# CompleteBoardAlternative.net
KiCad netlist of a schematic drawn in EAGLE
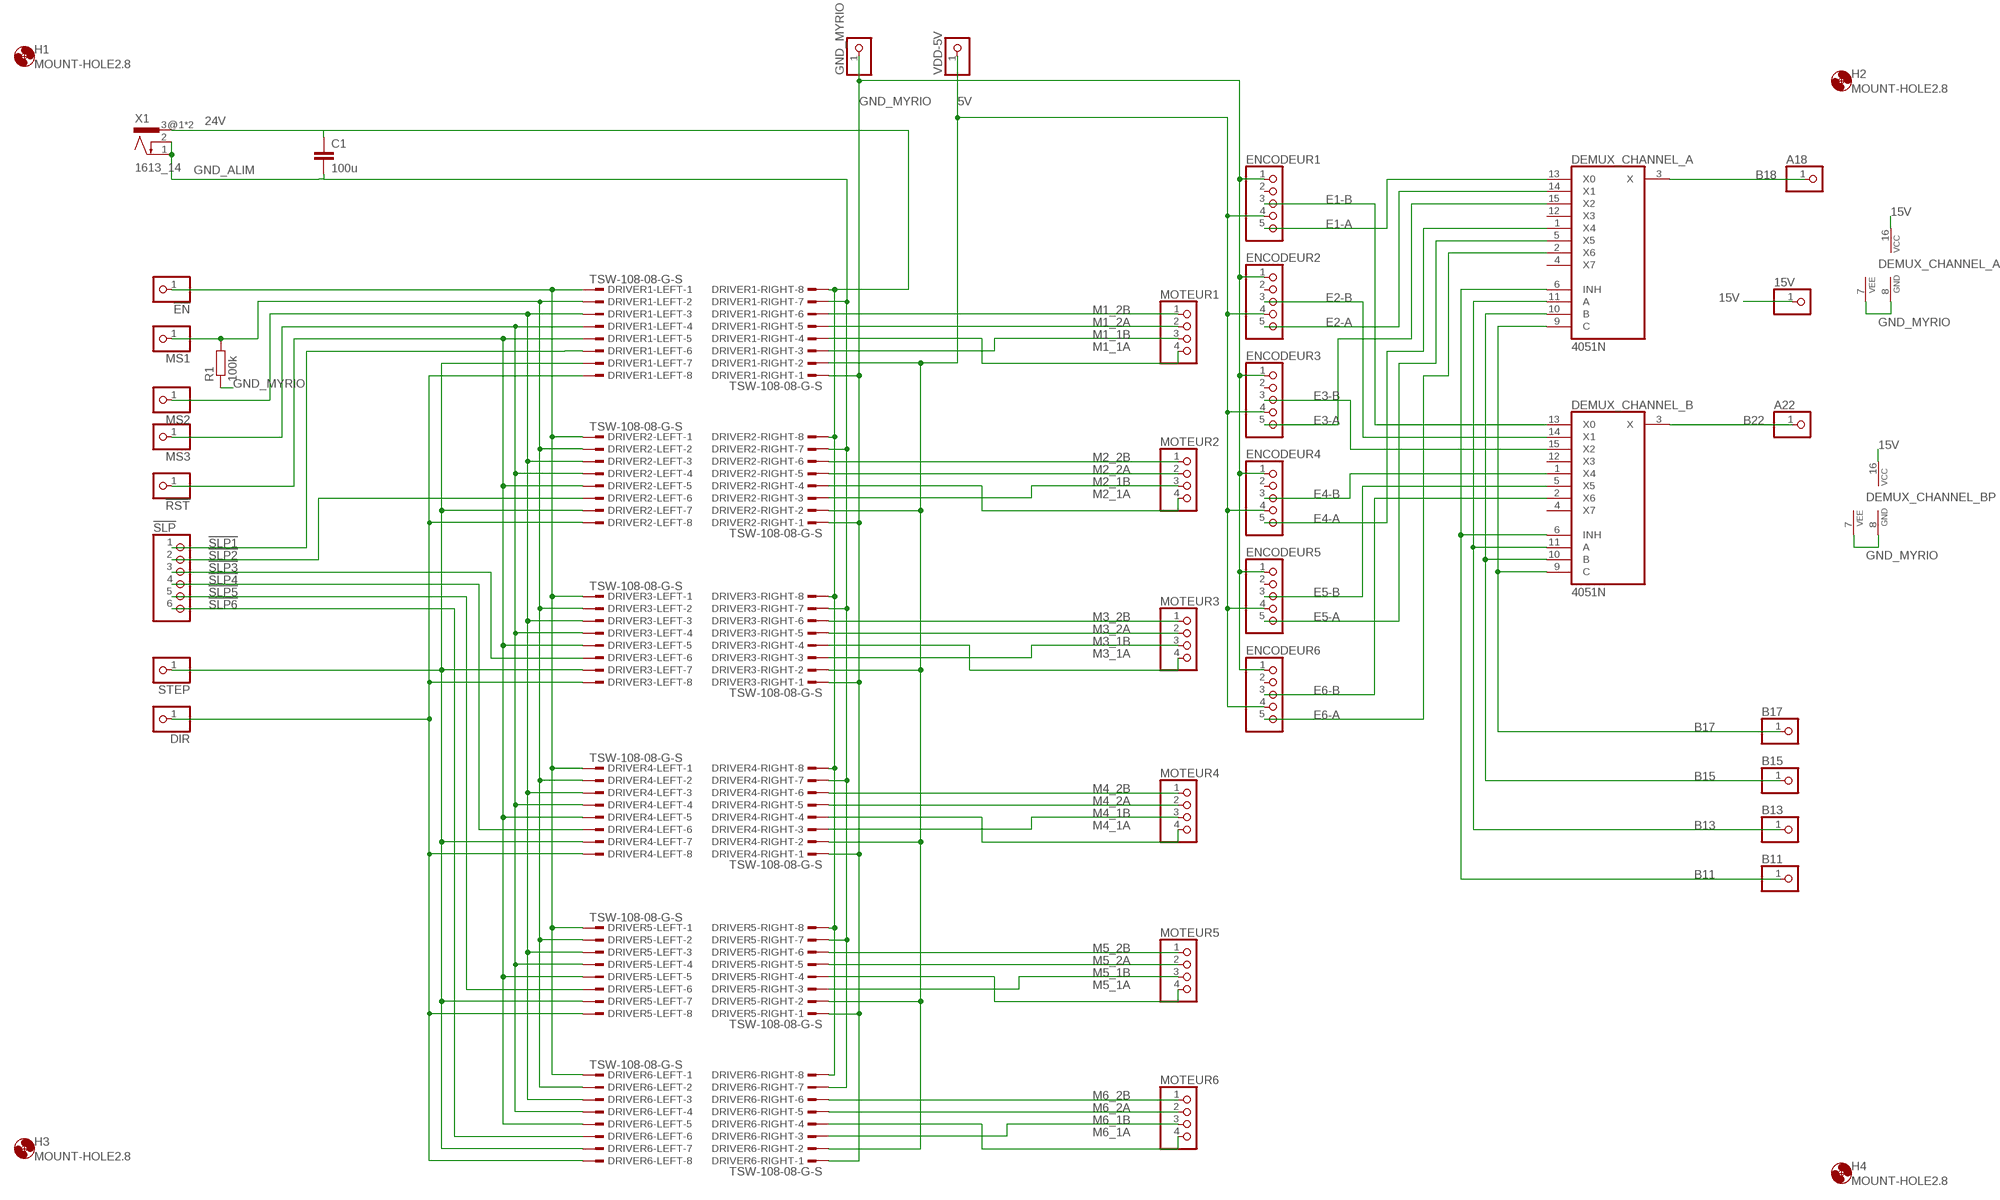
[diagram p0: schematic, sheet 1]

(export (version "E")
  (design (tool "Eeschema 10.0.6"))
  (components
    (comp (ref "!EN")
      (value "PINHD-1X1")
      (footprint "eagle-import:1X01")
      (libsource (lib "eagle-import") (part "PINHD-1X1"))
    )
    (comp (ref "!RST")
      (value "PINHD-1X1")
      (footprint "eagle-import:1X01")
      (libsource (lib "eagle-import") (part "PINHD-1X1"))
    )
    (comp (ref "!SLP")
      (value "PINHD-1X6")
      (footprint "eagle-import:1X06")
      (libsource (lib "eagle-import") (part "PINHD-1X6"))
    )
    (comp (ref "15V")
      (value "PINHD-1X1")
      (footprint "eagle-import:1X01")
      (libsource (lib "eagle-import") (part "PINHD-1X1"))
    )
    (comp (ref "A18")
      (value "PINHD-1X1")
      (footprint "eagle-import:1X01")
      (libsource (lib "eagle-import") (part "PINHD-1X1"))
    )
    (comp (ref "A22")
      (value "PINHD-1X1")
      (footprint "eagle-import:1X01")
      (libsource (lib "eagle-import") (part "PINHD-1X1"))
    )
    (comp (ref "B11")
      (value "PINHD-1X1")
      (footprint "eagle-import:1X01")
      (libsource (lib "eagle-import") (part "PINHD-1X1"))
    )
    (comp (ref "B13")
      (value "PINHD-1X1")
      (footprint "eagle-import:1X01")
      (libsource (lib "eagle-import") (part "PINHD-1X1"))
    )
    (comp (ref "B15")
      (value "PINHD-1X1")
      (footprint "eagle-import:1X01")
      (libsource (lib "eagle-import") (part "PINHD-1X1"))
    )
    (comp (ref "B17")
      (value "PINHD-1X1")
      (footprint "eagle-import:1X01")
      (libsource (lib "eagle-import") (part "PINHD-1X1"))
    )
    (comp (ref "C1")
      (value "100u")
      (footprint "eagle-import:C025-025X050")
      (libsource (lib "eagle-import") (part "C-EU025-025X050"))
    )
    (comp (ref "DEMUX_CHANNEL_A")
      (value "4051N")
      (footprint "eagle-import:DIL16")
      (libsource (lib "eagle-import") (part "4051N"))
    )
    (comp (ref "DEMUX_CHANNEL_B")
      (value "4051N")
      (footprint "eagle-import:DIL16")
      (libsource (lib "eagle-import") (part "4051N"))
    )
    (comp (ref "DIR")
      (value "PINHD-1X1")
      (footprint "eagle-import:1X01")
      (libsource (lib "eagle-import") (part "PINHD-1X1"))
    )
    (comp (ref "DRIVER1-LEFT")
      (value "TSW-108-08-G-S")
      (footprint "eagle-import:TSW-108-XX-G-S")
      (fields (field (name "MF") "Samtec Inc.") (field (name "MPN") "TSW-108-07-G-S"))
      (libsource (lib "eagle-import") (part "TSW-108--G-S08"))
    )
    (comp (ref "DRIVER1-RIGHT")
      (value "TSW-108-08-G-S")
      (footprint "eagle-import:TSW-108-XX-G-S")
      (fields (field (name "MF") "Samtec Inc.") (field (name "MPN") "TSW-108-07-G-S"))
      (libsource (lib "eagle-import") (part "TSW-108--G-S08"))
    )
    (comp (ref "DRIVER2-LEFT")
      (value "TSW-108-08-G-S")
      (footprint "eagle-import:TSW-108-XX-G-S")
      (fields (field (name "MF") "Samtec Inc.") (field (name "MPN") "TSW-108-07-G-S"))
      (libsource (lib "eagle-import") (part "TSW-108--G-S08"))
    )
    (comp (ref "DRIVER2-RIGHT")
      (value "TSW-108-08-G-S")
      (footprint "eagle-import:TSW-108-XX-G-S")
      (fields (field (name "MF") "Samtec Inc.") (field (name "MPN") "TSW-108-07-G-S"))
      (libsource (lib "eagle-import") (part "TSW-108--G-S08"))
    )
    (comp (ref "DRIVER3-LEFT")
      (value "TSW-108-08-G-S")
      (footprint "eagle-import:TSW-108-XX-G-S")
      (fields (field (name "MF") "Samtec Inc.") (field (name "MPN") "TSW-108-07-G-S"))
      (libsource (lib "eagle-import") (part "TSW-108--G-S08"))
    )
    (comp (ref "DRIVER3-RIGHT")
      (value "TSW-108-08-G-S")
      (footprint "eagle-import:TSW-108-XX-G-S")
      (fields (field (name "MF") "Samtec Inc.") (field (name "MPN") "TSW-108-07-G-S"))
      (libsource (lib "eagle-import") (part "TSW-108--G-S08"))
    )
    (comp (ref "DRIVER4-LEFT")
      (value "TSW-108-08-G-S")
      (footprint "eagle-import:TSW-108-XX-G-S")
      (fields (field (name "MF") "Samtec Inc.") (field (name "MPN") "TSW-108-07-G-S"))
      (libsource (lib "eagle-import") (part "TSW-108--G-S08"))
    )
    (comp (ref "DRIVER4-RIGHT")
      (value "TSW-108-08-G-S")
      (footprint "eagle-import:TSW-108-XX-G-S")
      (fields (field (name "MF") "Samtec Inc.") (field (name "MPN") "TSW-108-07-G-S"))
      (libsource (lib "eagle-import") (part "TSW-108--G-S08"))
    )
    (comp (ref "DRIVER5-LEFT")
      (value "TSW-108-08-G-S")
      (footprint "eagle-import:TSW-108-XX-G-S")
      (fields (field (name "MF") "Samtec Inc.") (field (name "MPN") "TSW-108-07-G-S"))
      (libsource (lib "eagle-import") (part "TSW-108--G-S08"))
    )
    (comp (ref "DRIVER5-RIGHT")
      (value "TSW-108-08-G-S")
      (footprint "eagle-import:TSW-108-XX-G-S")
      (fields (field (name "MF") "Samtec Inc.") (field (name "MPN") "TSW-108-07-G-S"))
      (libsource (lib "eagle-import") (part "TSW-108--G-S08"))
    )
    (comp (ref "DRIVER6-LEFT")
      (value "TSW-108-08-G-S")
      (footprint "eagle-import:TSW-108-XX-G-S")
      (fields (field (name "MF") "Samtec Inc.") (field (name "MPN") "TSW-108-07-G-S"))
      (libsource (lib "eagle-import") (part "TSW-108--G-S08"))
    )
    (comp (ref "DRIVER6-RIGHT")
      (value "TSW-108-08-G-S")
      (footprint "eagle-import:TSW-108-XX-G-S")
      (fields (field (name "MF") "Samtec Inc.") (field (name "MPN") "TSW-108-07-G-S"))
      (libsource (lib "eagle-import") (part "TSW-108--G-S08"))
    )
    (comp (ref "ENCODEUR1")
      (value "PINHD-1X5")
      (footprint "eagle-import:1X05")
      (libsource (lib "eagle-import") (part "PINHD-1X5"))
    )
    (comp (ref "ENCODEUR2")
      (value "PINHD-1X5")
      (footprint "eagle-import:1X05")
      (libsource (lib "eagle-import") (part "PINHD-1X5"))
    )
    (comp (ref "ENCODEUR3")
      (value "PINHD-1X5")
      (footprint "eagle-import:1X05")
      (libsource (lib "eagle-import") (part "PINHD-1X5"))
    )
    (comp (ref "ENCODEUR4")
      (value "PINHD-1X5")
      (footprint "eagle-import:1X05")
      (libsource (lib "eagle-import") (part "PINHD-1X5"))
    )
    (comp (ref "ENCODEUR5")
      (value "PINHD-1X5")
      (footprint "eagle-import:1X05")
      (libsource (lib "eagle-import") (part "PINHD-1X5"))
    )
    (comp (ref "ENCODEUR6")
      (value "PINHD-1X5")
      (footprint "eagle-import:1X05")
      (libsource (lib "eagle-import") (part "PINHD-1X5"))
    )
    (comp (ref "GND_MYRIO")
      (value "PINHD-1X1")
      (footprint "eagle-import:1X01")
      (libsource (lib "eagle-import") (part "PINHD-1X1"))
    )
    (comp (ref "H1")
      (value "MOUNT-HOLE2.8")
      (footprint "eagle-import:2,8")
      (libsource (lib "eagle-import") (part "MOUNT-HOLE2.8"))
    )
    (comp (ref "H2")
      (value "MOUNT-HOLE2.8")
      (footprint "eagle-import:2,8")
      (libsource (lib "eagle-import") (part "MOUNT-HOLE2.8"))
    )
    (comp (ref "H3")
      (value "MOUNT-HOLE2.8")
      (footprint "eagle-import:2,8")
      (libsource (lib "eagle-import") (part "MOUNT-HOLE2.8"))
    )
    (comp (ref "H4")
      (value "MOUNT-HOLE2.8")
      (footprint "eagle-import:2,8")
      (libsource (lib "eagle-import") (part "MOUNT-HOLE2.8"))
    )
    (comp (ref "MOTEUR1")
      (value "PINHD-1X4")
      (footprint "eagle-import:1X04")
      (libsource (lib "eagle-import") (part "PINHD-1X4"))
    )
    (comp (ref "MOTEUR2")
      (value "PINHD-1X4")
      (footprint "eagle-import:1X04")
      (libsource (lib "eagle-import") (part "PINHD-1X4"))
    )
    (comp (ref "MOTEUR3")
      (value "PINHD-1X4")
      (footprint "eagle-import:1X04")
      (libsource (lib "eagle-import") (part "PINHD-1X4"))
    )
    (comp (ref "MOTEUR4")
      (value "PINHD-1X4")
      (footprint "eagle-import:1X04")
      (libsource (lib "eagle-import") (part "PINHD-1X4"))
    )
    (comp (ref "MOTEUR5")
      (value "PINHD-1X4")
      (footprint "eagle-import:1X04")
      (libsource (lib "eagle-import") (part "PINHD-1X4"))
    )
    (comp (ref "MOTEUR6")
      (value "PINHD-1X4")
      (footprint "eagle-import:1X04")
      (libsource (lib "eagle-import") (part "PINHD-1X4"))
    )
    (comp (ref "MS1")
      (value "PINHD-1X1")
      (footprint "eagle-import:1X01")
      (libsource (lib "eagle-import") (part "PINHD-1X1"))
    )
    (comp (ref "MS2")
      (value "PINHD-1X1")
      (footprint "eagle-import:1X01")
      (libsource (lib "eagle-import") (part "PINHD-1X1"))
    )
    (comp (ref "MS3")
      (value "PINHD-1X1")
      (footprint "eagle-import:1X01")
      (libsource (lib "eagle-import") (part "PINHD-1X1"))
    )
    (comp (ref "R1")
      (value "100k")
      (footprint "eagle-import:0207_10")
      (libsource (lib "eagle-import") (part "R-EU_0207/10"))
    )
    (comp (ref "STEP")
      (value "PINHD-1X1")
      (footprint "eagle-import:1X01")
      (libsource (lib "eagle-import") (part "PINHD-1X1"))
    )
    (comp (ref "VDD-5V")
      (value "PINHD-1X1")
      (footprint "eagle-import:1X01")
      (libsource (lib "eagle-import") (part "PINHD-1X1"))
    )
    (comp (ref "X1")
      (value "1613_14")
      (footprint "eagle-import:1613_14")
      (fields (field (name "MF") "LUMBERG") (field (name "MPN") "1613 14"))
      (libsource (lib "eagle-import") (part "1613_14"))
    )
  )
  (nets
    (net (code "1") (name "/5V") (class "Default")
      (node (ref "DRIVER1-RIGHT") (pin "2") (pinfunction "1_2") (pintype "passive"))
      (node (ref "DRIVER2-RIGHT") (pin "2") (pinfunction "1_2") (pintype "passive"))
      (node (ref "DRIVER3-RIGHT") (pin "2") (pinfunction "1_2") (pintype "passive"))
      (node (ref "DRIVER4-RIGHT") (pin "2") (pinfunction "1_2") (pintype "passive"))
      (node (ref "DRIVER5-RIGHT") (pin "2") (pinfunction "1_2") (pintype "passive"))
      (node (ref "DRIVER6-RIGHT") (pin "2") (pinfunction "1_2") (pintype "passive"))
      (node (ref "ENCODEUR1") (pin "4") (pinfunction "4_4") (pintype "passive"))
      (node (ref "ENCODEUR2") (pin "4") (pinfunction "4_4") (pintype "passive"))
      (node (ref "ENCODEUR3") (pin "4") (pinfunction "4_4") (pintype "passive"))
      (node (ref "ENCODEUR4") (pin "4") (pinfunction "4_4") (pintype "passive"))
      (node (ref "ENCODEUR5") (pin "4") (pinfunction "4_4") (pintype "passive"))
      (node (ref "ENCODEUR6") (pin "4") (pinfunction "4_4") (pintype "passive"))
      (node (ref "VDD-5V") (pin "1") (pinfunction "1_1") (pintype "passive"))
    )
    (net (code "2") (name "/15V") (class "Default")
      (node (ref "15V") (pin "1") (pinfunction "1_1") (pintype "passive"))
      (node (ref "DEMUX_CHANNEL_A") (pin "16") (pinfunction "VCC_16") (pintype "power_in"))
      (node (ref "DEMUX_CHANNEL_B") (pin "16") (pinfunction "VCC_16") (pintype "power_in"))
    )
    (net (code "3") (name "/24V") (class "Default")
      (node (ref "C1") (pin "1") (pinfunction "1_1") (pintype "passive"))
      (node (ref "DRIVER1-RIGHT") (pin "8") (pinfunction "1_8") (pintype "passive"))
      (node (ref "DRIVER2-RIGHT") (pin "8") (pinfunction "1_8") (pintype "passive"))
      (node (ref "DRIVER3-RIGHT") (pin "8") (pinfunction "1_8") (pintype "passive"))
      (node (ref "DRIVER4-RIGHT") (pin "8") (pinfunction "1_8") (pintype "passive"))
      (node (ref "DRIVER5-RIGHT") (pin "8") (pinfunction "1_8") (pintype "passive"))
      (node (ref "DRIVER6-RIGHT") (pin "8") (pinfunction "1_8") (pintype "passive"))
      (node (ref "X1") (pin "3@1") (pinfunction "3_3@1") (pintype "passive"))
      (node (ref "X1") (pin "3@2") (pinfunction "3_3@2") (pintype "passive"))
    )
    (net (code "4") (name "/B11") (class "Default")
      (node (ref "B11") (pin "1") (pinfunction "1_1") (pintype "passive"))
      (node (ref "DEMUX_CHANNEL_A") (pin "6") (pinfunction "INH_6") (pintype "input"))
      (node (ref "DEMUX_CHANNEL_B") (pin "6") (pinfunction "INH_6") (pintype "input"))
    )
    (net (code "5") (name "/B13") (class "Default")
      (node (ref "B13") (pin "1") (pinfunction "1_1") (pintype "passive"))
      (node (ref "DEMUX_CHANNEL_A") (pin "11") (pinfunction "A_11") (pintype "input"))
      (node (ref "DEMUX_CHANNEL_B") (pin "11") (pinfunction "A_11") (pintype "input"))
    )
    (net (code "6") (name "/B15") (class "Default")
      (node (ref "B15") (pin "1") (pinfunction "1_1") (pintype "passive"))
      (node (ref "DEMUX_CHANNEL_A") (pin "10") (pinfunction "B_10") (pintype "input"))
      (node (ref "DEMUX_CHANNEL_B") (pin "10") (pinfunction "B_10") (pintype "input"))
    )
    (net (code "7") (name "/B17") (class "Default")
      (node (ref "B17") (pin "1") (pinfunction "1_1") (pintype "passive"))
      (node (ref "DEMUX_CHANNEL_A") (pin "9") (pinfunction "C_9") (pintype "input"))
      (node (ref "DEMUX_CHANNEL_B") (pin "9") (pinfunction "C_9") (pintype "input"))
    )
    (net (code "8") (name "/B18") (class "Default")
      (node (ref "A18") (pin "1") (pinfunction "1_1") (pintype "passive"))
      (node (ref "DEMUX_CHANNEL_A") (pin "3") (pinfunction "X_3") (pintype "bidirectional"))
    )
    (net (code "9") (name "/B22") (class "Default")
      (node (ref "A22") (pin "1") (pinfunction "1_1") (pintype "passive"))
      (node (ref "DEMUX_CHANNEL_B") (pin "3") (pinfunction "X_3") (pintype "bidirectional"))
    )
    (net (code "10") (name "/E1-A") (class "Default")
      (node (ref "DEMUX_CHANNEL_A") (pin "13") (pinfunction "X0_13") (pintype "bidirectional"))
      (node (ref "ENCODEUR1") (pin "5") (pinfunction "5_5") (pintype "passive"))
    )
    (net (code "11") (name "/E1-B") (class "Default")
      (node (ref "DEMUX_CHANNEL_B") (pin "13") (pinfunction "X0_13") (pintype "bidirectional"))
      (node (ref "ENCODEUR1") (pin "3") (pinfunction "3_3") (pintype "passive"))
    )
    (net (code "12") (name "/E2-A") (class "Default")
      (node (ref "DEMUX_CHANNEL_A") (pin "14") (pinfunction "X1_14") (pintype "bidirectional"))
      (node (ref "ENCODEUR2") (pin "5") (pinfunction "5_5") (pintype "passive"))
    )
    (net (code "13") (name "/E2-B") (class "Default")
      (node (ref "DEMUX_CHANNEL_B") (pin "14") (pinfunction "X1_14") (pintype "bidirectional"))
      (node (ref "ENCODEUR2") (pin "3") (pinfunction "3_3") (pintype "passive"))
    )
    (net (code "14") (name "/E3-A") (class "Default")
      (node (ref "DEMUX_CHANNEL_A") (pin "15") (pinfunction "X2_15") (pintype "bidirectional"))
      (node (ref "ENCODEUR3") (pin "5") (pinfunction "5_5") (pintype "passive"))
    )
    (net (code "15") (name "/E3-B") (class "Default")
      (node (ref "DEMUX_CHANNEL_B") (pin "15") (pinfunction "X2_15") (pintype "bidirectional"))
      (node (ref "ENCODEUR3") (pin "3") (pinfunction "3_3") (pintype "passive"))
    )
    (net (code "16") (name "/E4-A") (class "Default")
      (node (ref "DEMUX_CHANNEL_A") (pin "1") (pinfunction "X4_1") (pintype "bidirectional"))
      (node (ref "ENCODEUR4") (pin "5") (pinfunction "5_5") (pintype "passive"))
    )
    (net (code "17") (name "/E4-B") (class "Default")
      (node (ref "DEMUX_CHANNEL_B") (pin "1") (pinfunction "X4_1") (pintype "bidirectional"))
      (node (ref "ENCODEUR4") (pin "3") (pinfunction "3_3") (pintype "passive"))
    )
    (net (code "18") (name "/E5-A") (class "Default")
      (node (ref "DEMUX_CHANNEL_A") (pin "5") (pinfunction "X5_5") (pintype "bidirectional"))
      (node (ref "ENCODEUR5") (pin "5") (pinfunction "5_5") (pintype "passive"))
    )
    (net (code "19") (name "/E5-B") (class "Default")
      (node (ref "DEMUX_CHANNEL_B") (pin "5") (pinfunction "X5_5") (pintype "bidirectional"))
      (node (ref "ENCODEUR5") (pin "3") (pinfunction "3_3") (pintype "passive"))
    )
    (net (code "20") (name "/E6-A") (class "Default")
      (node (ref "DEMUX_CHANNEL_A") (pin "2") (pinfunction "X6_2") (pintype "bidirectional"))
      (node (ref "ENCODEUR6") (pin "5") (pinfunction "5_5") (pintype "passive"))
    )
    (net (code "21") (name "/E6-B") (class "Default")
      (node (ref "DEMUX_CHANNEL_B") (pin "2") (pinfunction "X6_2") (pintype "bidirectional"))
      (node (ref "ENCODEUR6") (pin "3") (pinfunction "3_3") (pintype "passive"))
    )
    (net (code "22") (name "/GND_ALIM") (class "Default")
      (node (ref "C1") (pin "2") (pinfunction "2_2") (pintype "passive"))
      (node (ref "DRIVER1-RIGHT") (pin "7") (pinfunction "1_7") (pintype "passive"))
      (node (ref "DRIVER2-RIGHT") (pin "7") (pinfunction "1_7") (pintype "passive"))
      (node (ref "DRIVER3-RIGHT") (pin "7") (pinfunction "1_7") (pintype "passive"))
      (node (ref "DRIVER4-RIGHT") (pin "7") (pinfunction "1_7") (pintype "passive"))
      (node (ref "DRIVER5-RIGHT") (pin "7") (pinfunction "1_7") (pintype "passive"))
      (node (ref "DRIVER6-RIGHT") (pin "7") (pinfunction "1_7") (pintype "passive"))
      (node (ref "X1") (pin "1") (pinfunction "1_1") (pintype "passive"))
      (node (ref "X1") (pin "2") (pinfunction "2_2") (pintype "passive"))
    )
    (net (code "23") (name "/GND_MYRIO") (class "Default")
      (node (ref "DEMUX_CHANNEL_A") (pin "7") (pinfunction "VEE_7") (pintype "power_in"))
      (node (ref "DEMUX_CHANNEL_A") (pin "8") (pinfunction "GND_8") (pintype "power_in"))
      (node (ref "DEMUX_CHANNEL_B") (pin "7") (pinfunction "VEE_7") (pintype "power_in"))
      (node (ref "DEMUX_CHANNEL_B") (pin "8") (pinfunction "GND_8") (pintype "power_in"))
      (node (ref "DRIVER1-RIGHT") (pin "1") (pinfunction "1_1") (pintype "passive"))
      (node (ref "DRIVER2-RIGHT") (pin "1") (pinfunction "1_1") (pintype "passive"))
      (node (ref "DRIVER3-RIGHT") (pin "1") (pinfunction "1_1") (pintype "passive"))
      (node (ref "DRIVER4-RIGHT") (pin "1") (pinfunction "1_1") (pintype "passive"))
      (node (ref "DRIVER5-RIGHT") (pin "1") (pinfunction "1_1") (pintype "passive"))
      (node (ref "DRIVER6-RIGHT") (pin "1") (pinfunction "1_1") (pintype "passive"))
      (node (ref "ENCODEUR1") (pin "1") (pinfunction "1_1") (pintype "passive"))
      (node (ref "ENCODEUR2") (pin "1") (pinfunction "1_1") (pintype "passive"))
      (node (ref "ENCODEUR3") (pin "1") (pinfunction "1_1") (pintype "passive"))
      (node (ref "ENCODEUR4") (pin "1") (pinfunction "1_1") (pintype "passive"))
      (node (ref "ENCODEUR5") (pin "1") (pinfunction "1_1") (pintype "passive"))
      (node (ref "ENCODEUR6") (pin "1") (pinfunction "1_1") (pintype "passive"))
      (node (ref "GND_MYRIO") (pin "1") (pinfunction "1_1") (pintype "passive"))
      (node (ref "R1") (pin "1") (pinfunction "1_1") (pintype "passive"))
    )
    (net (code "24") (name "/M1_1A") (class "Default")
      (node (ref "DRIVER1-RIGHT") (pin "4") (pinfunction "1_4") (pintype "passive"))
      (node (ref "MOTEUR1") (pin "4") (pinfunction "4_4") (pintype "passive"))
    )
    (net (code "25") (name "/M1_1B") (class "Default")
      (node (ref "DRIVER1-RIGHT") (pin "3") (pinfunction "1_3") (pintype "passive"))
      (node (ref "MOTEUR1") (pin "3") (pinfunction "3_3") (pintype "passive"))
    )
    (net (code "26") (name "/M1_2A") (class "Default")
      (node (ref "DRIVER1-RIGHT") (pin "5") (pinfunction "1_5") (pintype "passive"))
      (node (ref "MOTEUR1") (pin "2") (pinfunction "2_2") (pintype "passive"))
    )
    (net (code "27") (name "/M1_2B") (class "Default")
      (node (ref "DRIVER1-RIGHT") (pin "6") (pinfunction "1_6") (pintype "passive"))
      (node (ref "MOTEUR1") (pin "1") (pinfunction "1_1") (pintype "passive"))
    )
    (net (code "28") (name "/M2_1A") (class "Default")
      (node (ref "DRIVER2-RIGHT") (pin "4") (pinfunction "1_4") (pintype "passive"))
      (node (ref "MOTEUR2") (pin "4") (pinfunction "4_4") (pintype "passive"))
    )
    (net (code "29") (name "/M2_1B") (class "Default")
      (node (ref "DRIVER2-RIGHT") (pin "3") (pinfunction "1_3") (pintype "passive"))
      (node (ref "MOTEUR2") (pin "3") (pinfunction "3_3") (pintype "passive"))
    )
    (net (code "30") (name "/M2_2A") (class "Default")
      (node (ref "DRIVER2-RIGHT") (pin "5") (pinfunction "1_5") (pintype "passive"))
      (node (ref "MOTEUR2") (pin "2") (pinfunction "2_2") (pintype "passive"))
    )
    (net (code "31") (name "/M2_2B") (class "Default")
      (node (ref "DRIVER2-RIGHT") (pin "6") (pinfunction "1_6") (pintype "passive"))
      (node (ref "MOTEUR2") (pin "1") (pinfunction "1_1") (pintype "passive"))
    )
    (net (code "32") (name "/M3_1A") (class "Default")
      (node (ref "DRIVER3-RIGHT") (pin "4") (pinfunction "1_4") (pintype "passive"))
      (node (ref "MOTEUR3") (pin "4") (pinfunction "4_4") (pintype "passive"))
    )
    (net (code "33") (name "/M3_1B") (class "Default")
      (node (ref "DRIVER3-RIGHT") (pin "3") (pinfunction "1_3") (pintype "passive"))
      (node (ref "MOTEUR3") (pin "3") (pinfunction "3_3") (pintype "passive"))
    )
    (net (code "34") (name "/M3_2A") (class "Default")
      (node (ref "DRIVER3-RIGHT") (pin "5") (pinfunction "1_5") (pintype "passive"))
      (node (ref "MOTEUR3") (pin "2") (pinfunction "2_2") (pintype "passive"))
    )
    (net (code "35") (name "/M3_2B") (class "Default")
      (node (ref "DRIVER3-RIGHT") (pin "6") (pinfunction "1_6") (pintype "passive"))
      (node (ref "MOTEUR3") (pin "1") (pinfunction "1_1") (pintype "passive"))
    )
    (net (code "36") (name "/M4_1A") (class "Default")
      (node (ref "DRIVER4-RIGHT") (pin "4") (pinfunction "1_4") (pintype "passive"))
      (node (ref "MOTEUR4") (pin "4") (pinfunction "4_4") (pintype "passive"))
    )
    (net (code "37") (name "/M4_1B") (class "Default")
      (node (ref "DRIVER4-RIGHT") (pin "3") (pinfunction "1_3") (pintype "passive"))
      (node (ref "MOTEUR4") (pin "3") (pinfunction "3_3") (pintype "passive"))
    )
    (net (code "38") (name "/M4_2A") (class "Default")
      (node (ref "DRIVER4-RIGHT") (pin "5") (pinfunction "1_5") (pintype "passive"))
      (node (ref "MOTEUR4") (pin "2") (pinfunction "2_2") (pintype "passive"))
    )
    (net (code "39") (name "/M4_2B") (class "Default")
      (node (ref "DRIVER4-RIGHT") (pin "6") (pinfunction "1_6") (pintype "passive"))
      (node (ref "MOTEUR4") (pin "1") (pinfunction "1_1") (pintype "passive"))
    )
    (net (code "40") (name "/M5_1A") (class "Default")
      (node (ref "DRIVER5-RIGHT") (pin "4") (pinfunction "1_4") (pintype "passive"))
      (node (ref "MOTEUR5") (pin "4") (pinfunction "4_4") (pintype "passive"))
    )
    (net (code "41") (name "/M5_1B") (class "Default")
      (node (ref "DRIVER5-RIGHT") (pin "3") (pinfunction "1_3") (pintype "passive"))
      (node (ref "MOTEUR5") (pin "3") (pinfunction "3_3") (pintype "passive"))
    )
    (net (code "42") (name "/M5_2A") (class "Default")
      (node (ref "DRIVER5-RIGHT") (pin "5") (pinfunction "1_5") (pintype "passive"))
      (node (ref "MOTEUR5") (pin "2") (pinfunction "2_2") (pintype "passive"))
    )
    (net (code "43") (name "/M5_2B") (class "Default")
      (node (ref "DRIVER5-RIGHT") (pin "6") (pinfunction "1_6") (pintype "passive"))
      (node (ref "MOTEUR5") (pin "1") (pinfunction "1_1") (pintype "passive"))
    )
    (net (code "44") (name "/M6_1A") (class "Default")
      (node (ref "DRIVER6-RIGHT") (pin "4") (pinfunction "1_4") (pintype "passive"))
      (node (ref "MOTEUR6") (pin "4") (pinfunction "4_4") (pintype "passive"))
    )
    (net (code "45") (name "/M6_1B") (class "Default")
      (node (ref "DRIVER6-RIGHT") (pin "3") (pinfunction "1_3") (pintype "passive"))
      (node (ref "MOTEUR6") (pin "3") (pinfunction "3_3") (pintype "passive"))
    )
    (net (code "46") (name "/M6_2A") (class "Default")
      (node (ref "DRIVER6-RIGHT") (pin "5") (pinfunction "1_5") (pintype "passive"))
      (node (ref "MOTEUR6") (pin "2") (pinfunction "2_2") (pintype "passive"))
    )
    (net (code "47") (name "/M6_2B") (class "Default")
      (node (ref "DRIVER6-RIGHT") (pin "6") (pinfunction "1_6") (pintype "passive"))
      (node (ref "MOTEUR6") (pin "1") (pinfunction "1_1") (pintype "passive"))
    )
    (net (code "48") (name "/~{SLP1}") (class "Default")
      (node (ref "!SLP") (pin "1") (pinfunction "1_1") (pintype "passive"))
      (node (ref "DRIVER1-LEFT") (pin "6") (pinfunction "1_6") (pintype "passive"))
    )
    (net (code "49") (name "/~{SLP2}") (class "Default")
      (node (ref "!SLP") (pin "2") (pinfunction "2_2") (pintype "passive"))
      (node (ref "DRIVER2-LEFT") (pin "6") (pinfunction "1_6") (pintype "passive"))
    )
    (net (code "50") (name "/~{SLP3}") (class "Default")
      (node (ref "!SLP") (pin "3") (pinfunction "3_3") (pintype "passive"))
      (node (ref "DRIVER3-LEFT") (pin "6") (pinfunction "1_6") (pintype "passive"))
    )
    (net (code "51") (name "/~{SLP4}") (class "Default")
      (node (ref "!SLP") (pin "4") (pinfunction "4_4") (pintype "passive"))
      (node (ref "DRIVER4-LEFT") (pin "6") (pinfunction "1_6") (pintype "passive"))
    )
    (net (code "52") (name "/~{SLP5}") (class "Default")
      (node (ref "!SLP") (pin "5") (pinfunction "5_5") (pintype "passive"))
      (node (ref "DRIVER5-LEFT") (pin "6") (pinfunction "1_6") (pintype "passive"))
    )
    (net (code "53") (name "/~{SLP6}") (class "Default")
      (node (ref "!SLP") (pin "6") (pinfunction "6_6") (pintype "passive"))
      (node (ref "DRIVER6-LEFT") (pin "6") (pinfunction "1_6") (pintype "passive"))
    )
    (net (code "54") (name "Net-(!EN-Pad1)") (class "Default")
      (node (ref "!EN") (pin "1") (pinfunction "1_1") (pintype "passive"))
      (node (ref "DRIVER1-LEFT") (pin "1") (pinfunction "1_1") (pintype "passive"))
      (node (ref "DRIVER2-LEFT") (pin "1") (pinfunction "1_1") (pintype "passive"))
      (node (ref "DRIVER3-LEFT") (pin "1") (pinfunction "1_1") (pintype "passive"))
      (node (ref "DRIVER4-LEFT") (pin "1") (pinfunction "1_1") (pintype "passive"))
      (node (ref "DRIVER5-LEFT") (pin "1") (pinfunction "1_1") (pintype "passive"))
      (node (ref "DRIVER6-LEFT") (pin "1") (pinfunction "1_1") (pintype "passive"))
    )
    (net (code "55") (name "Net-(DRIVER1-LEFTB-1)") (class "Default")
      (node (ref "DRIVER1-LEFT") (pin "2") (pinfunction "1_2") (pintype "passive"))
      (node (ref "DRIVER2-LEFT") (pin "2") (pinfunction "1_2") (pintype "passive"))
      (node (ref "DRIVER3-LEFT") (pin "2") (pinfunction "1_2") (pintype "passive"))
      (node (ref "DRIVER4-LEFT") (pin "2") (pinfunction "1_2") (pintype "passive"))
      (node (ref "DRIVER5-LEFT") (pin "2") (pinfunction "1_2") (pintype "passive"))
      (node (ref "DRIVER6-LEFT") (pin "2") (pinfunction "1_2") (pintype "passive"))
      (node (ref "MS1") (pin "1") (pinfunction "1_1") (pintype "passive"))
      (node (ref "R1") (pin "2") (pinfunction "2_2") (pintype "passive"))
    )
    (net (code "56") (name "Net-(DRIVER1-LEFTC-1)") (class "Default")
      (node (ref "DRIVER1-LEFT") (pin "3") (pinfunction "1_3") (pintype "passive"))
      (node (ref "DRIVER2-LEFT") (pin "3") (pinfunction "1_3") (pintype "passive"))
      (node (ref "DRIVER3-LEFT") (pin "3") (pinfunction "1_3") (pintype "passive"))
      (node (ref "DRIVER4-LEFT") (pin "3") (pinfunction "1_3") (pintype "passive"))
      (node (ref "DRIVER5-LEFT") (pin "3") (pinfunction "1_3") (pintype "passive"))
      (node (ref "DRIVER6-LEFT") (pin "3") (pinfunction "1_3") (pintype "passive"))
      (node (ref "MS2") (pin "1") (pinfunction "1_1") (pintype "passive"))
    )
    (net (code "57") (name "Net-(DRIVER1-LEFTD-1)") (class "Default")
      (node (ref "DRIVER1-LEFT") (pin "4") (pinfunction "1_4") (pintype "passive"))
      (node (ref "DRIVER2-LEFT") (pin "4") (pinfunction "1_4") (pintype "passive"))
      (node (ref "DRIVER3-LEFT") (pin "4") (pinfunction "1_4") (pintype "passive"))
      (node (ref "DRIVER4-LEFT") (pin "4") (pinfunction "1_4") (pintype "passive"))
      (node (ref "DRIVER5-LEFT") (pin "4") (pinfunction "1_4") (pintype "passive"))
      (node (ref "DRIVER6-LEFT") (pin "4") (pinfunction "1_4") (pintype "passive"))
      (node (ref "MS3") (pin "1") (pinfunction "1_1") (pintype "passive"))
    )
    (net (code "58") (name "Net-(DRIVER1-LEFTE-1)") (class "Default")
      (node (ref "!RST") (pin "1") (pinfunction "1_1") (pintype "passive"))
      (node (ref "DRIVER1-LEFT") (pin "5") (pinfunction "1_5") (pintype "passive"))
      (node (ref "DRIVER2-LEFT") (pin "5") (pinfunction "1_5") (pintype "passive"))
      (node (ref "DRIVER3-LEFT") (pin "5") (pinfunction "1_5") (pintype "passive"))
      (node (ref "DRIVER4-LEFT") (pin "5") (pinfunction "1_5") (pintype "passive"))
      (node (ref "DRIVER5-LEFT") (pin "5") (pinfunction "1_5") (pintype "passive"))
      (node (ref "DRIVER6-LEFT") (pin "5") (pinfunction "1_5") (pintype "passive"))
    )
    (net (code "59") (name "Net-(DRIVER1-LEFTG-1)") (class "Default")
      (node (ref "DRIVER1-LEFT") (pin "7") (pinfunction "1_7") (pintype "passive"))
      (node (ref "DRIVER2-LEFT") (pin "7") (pinfunction "1_7") (pintype "passive"))
      (node (ref "DRIVER3-LEFT") (pin "7") (pinfunction "1_7") (pintype "passive"))
      (node (ref "DRIVER4-LEFT") (pin "7") (pinfunction "1_7") (pintype "passive"))
      (node (ref "DRIVER5-LEFT") (pin "7") (pinfunction "1_7") (pintype "passive"))
      (node (ref "DRIVER6-LEFT") (pin "7") (pinfunction "1_7") (pintype "passive"))
      (node (ref "STEP") (pin "1") (pinfunction "1_1") (pintype "passive"))
    )
    (net (code "60") (name "Net-(DRIVER1-LEFTH-1)") (class "Default")
      (node (ref "DIR") (pin "1") (pinfunction "1_1") (pintype "passive"))
      (node (ref "DRIVER1-LEFT") (pin "8") (pinfunction "1_8") (pintype "passive"))
      (node (ref "DRIVER2-LEFT") (pin "8") (pinfunction "1_8") (pintype "passive"))
      (node (ref "DRIVER3-LEFT") (pin "8") (pinfunction "1_8") (pintype "passive"))
      (node (ref "DRIVER4-LEFT") (pin "8") (pinfunction "1_8") (pintype "passive"))
      (node (ref "DRIVER5-LEFT") (pin "8") (pinfunction "1_8") (pintype "passive"))
      (node (ref "DRIVER6-LEFT") (pin "8") (pinfunction "1_8") (pintype "passive"))
    )
    (net (code "61") (name "unconnected-(DEMUX_CHANNEL_AA-X3-Pad12)") (class "Default")
      (node (ref "DEMUX_CHANNEL_A") (pin "12") (pinfunction "X3_12") (pintype "bidirectional"))
    )
    (net (code "62") (name "unconnected-(DEMUX_CHANNEL_AA-X7-Pad4)") (class "Default")
      (node (ref "DEMUX_CHANNEL_A") (pin "4") (pinfunction "X7_4") (pintype "bidirectional"))
    )
    (net (code "63") (name "unconnected-(DEMUX_CHANNEL_BA-X3-Pad12)") (class "Default")
      (node (ref "DEMUX_CHANNEL_B") (pin "12") (pinfunction "X3_12") (pintype "bidirectional"))
    )
    (net (code "64") (name "unconnected-(DEMUX_CHANNEL_BA-X7-Pad4)") (class "Default")
      (node (ref "DEMUX_CHANNEL_B") (pin "4") (pinfunction "X7_4") (pintype "bidirectional"))
    )
    (net (code "65") (name "unconnected-(ENCODEUR1-Pad2)") (class "Default")
      (node (ref "ENCODEUR1") (pin "2") (pinfunction "2_2") (pintype "passive"))
    )
    (net (code "66") (name "unconnected-(ENCODEUR2-Pad2)") (class "Default")
      (node (ref "ENCODEUR2") (pin "2") (pinfunction "2_2") (pintype "passive"))
    )
    (net (code "67") (name "unconnected-(ENCODEUR3-Pad2)") (class "Default")
      (node (ref "ENCODEUR3") (pin "2") (pinfunction "2_2") (pintype "passive"))
    )
    (net (code "68") (name "unconnected-(ENCODEUR4-Pad2)") (class "Default")
      (node (ref "ENCODEUR4") (pin "2") (pinfunction "2_2") (pintype "passive"))
    )
    (net (code "69") (name "unconnected-(ENCODEUR5-Pad2)") (class "Default")
      (node (ref "ENCODEUR5") (pin "2") (pinfunction "2_2") (pintype "passive"))
    )
    (net (code "70") (name "unconnected-(ENCODEUR6-Pad2)") (class "Default")
      (node (ref "ENCODEUR6") (pin "2") (pinfunction "2_2") (pintype "passive"))
    )
  )
)
